# x4to1XTRXv13.net
KiCad netlist of a schematic drawn in Altium Designer
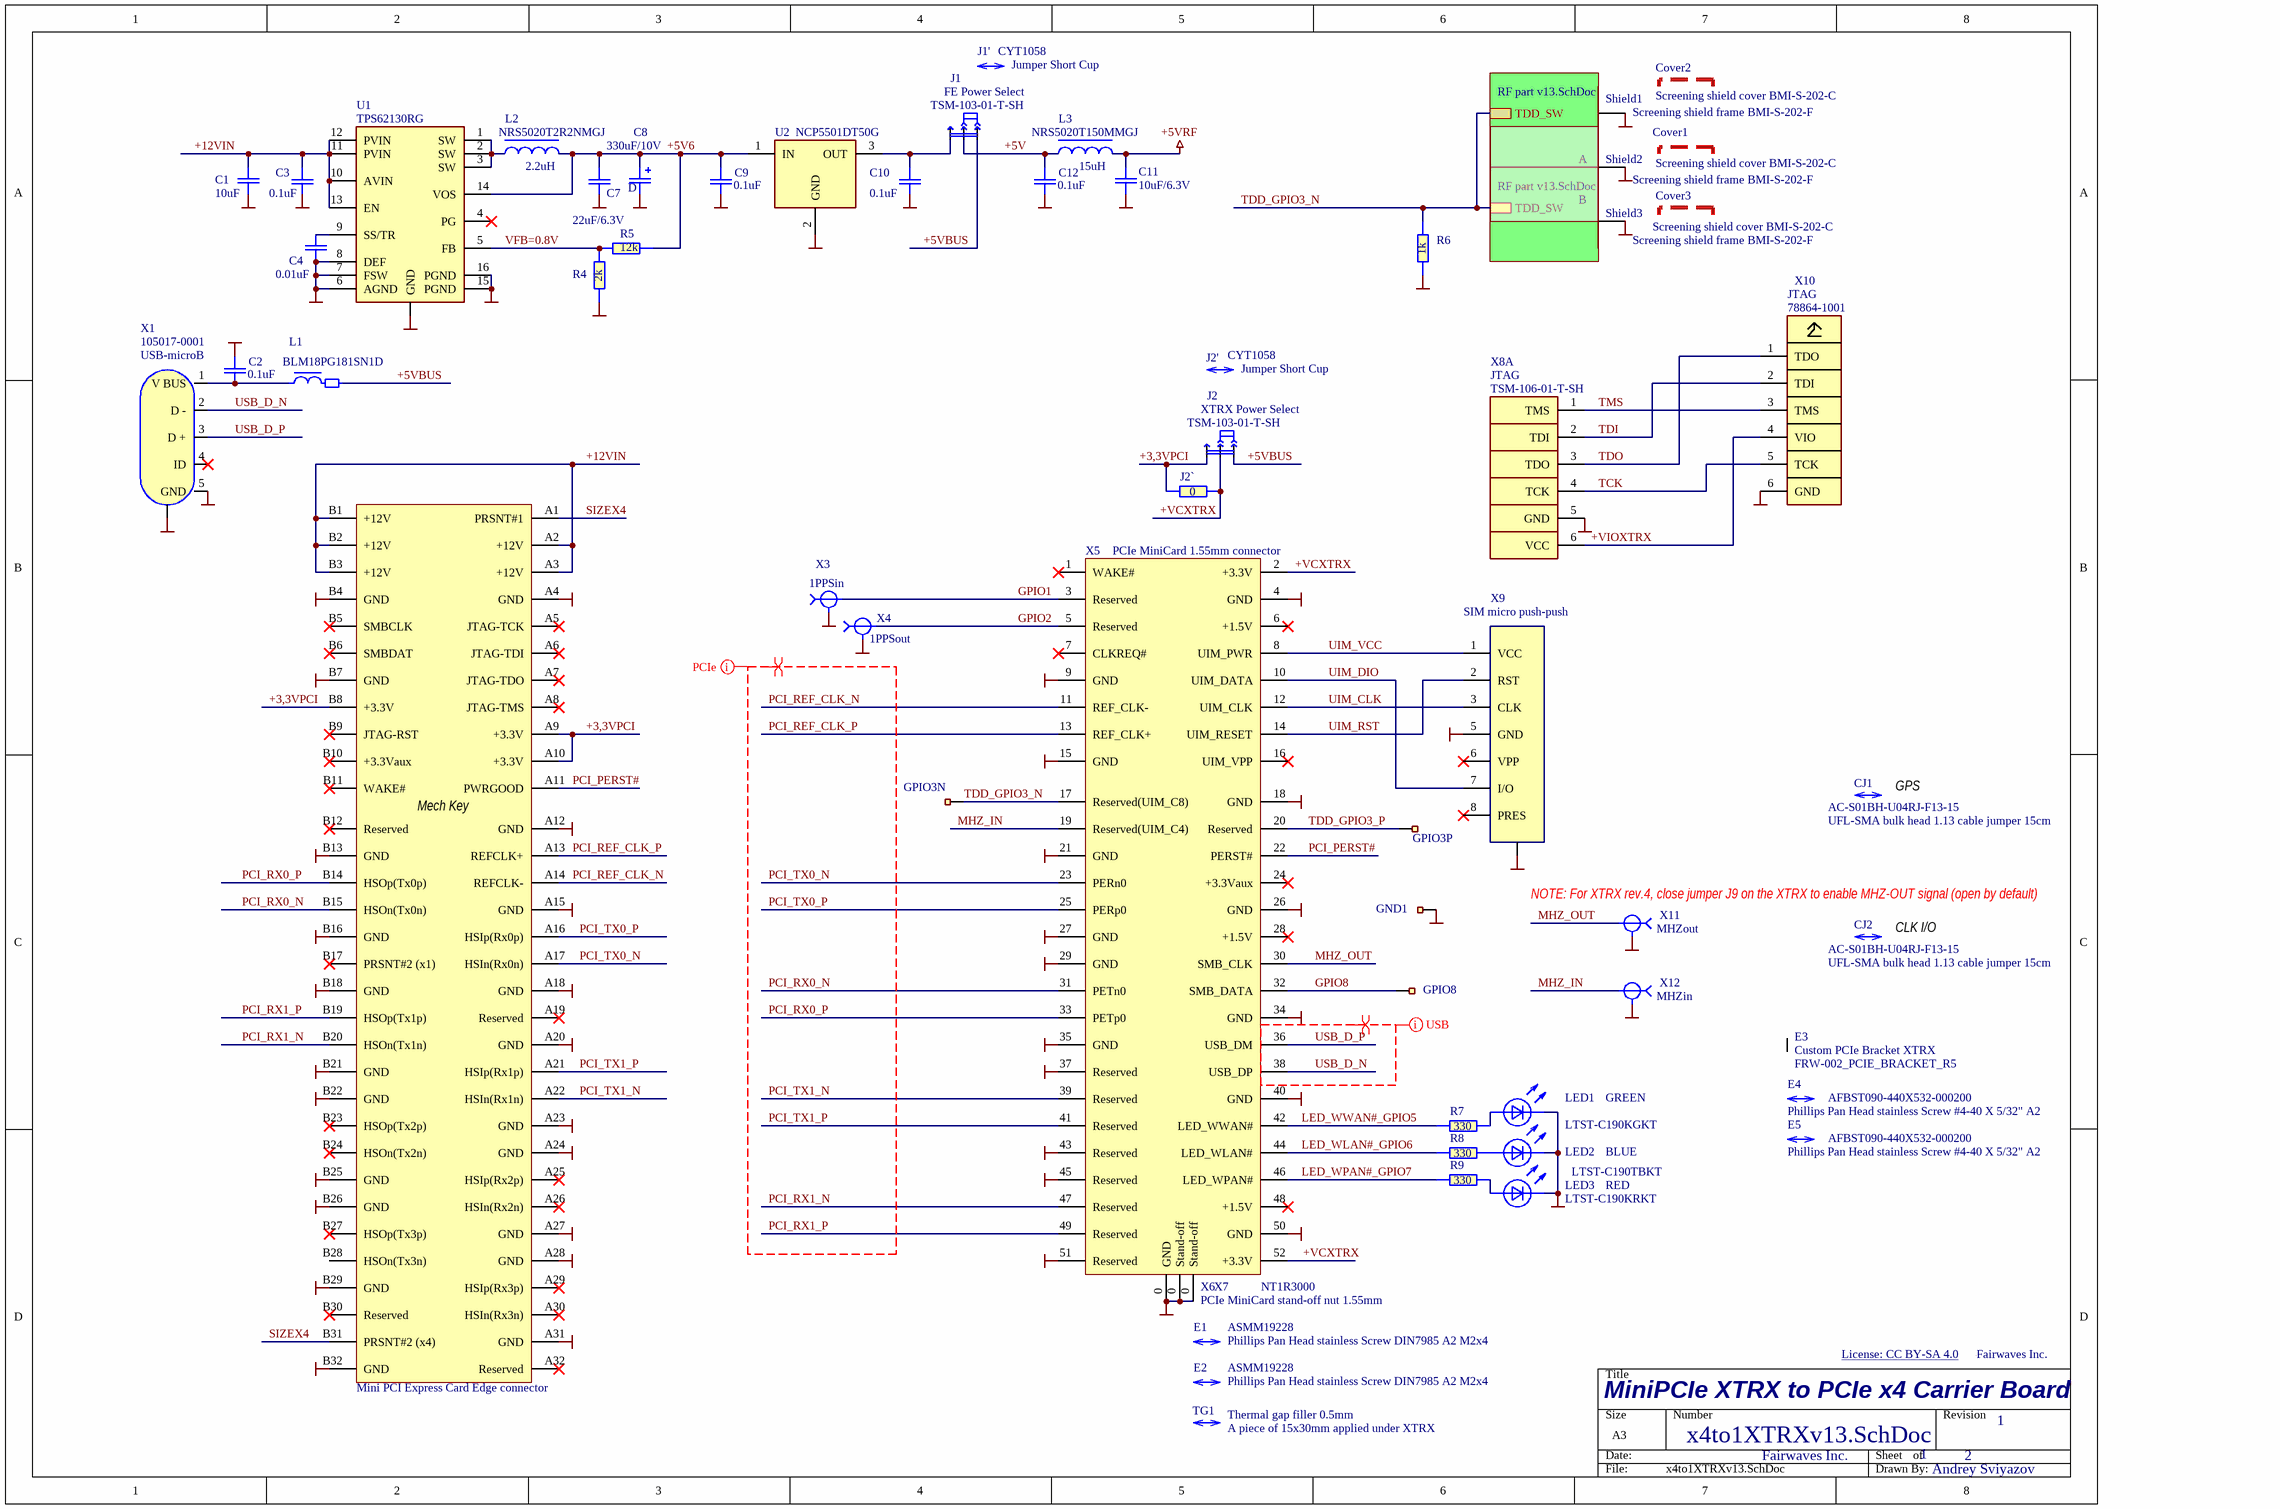
[diagram p0: x4to1XTRXv13.SchDoc]

(export (version "E")
  (design (tool "Eeschema 10.0.6"))
  (components
    (comp (ref "C1")
      (value "10uF")
      (footprint "C0805")
      (description "Capacitor")
      (fields (field (name "MANUFACTURER") "MURATA") (field (name "TOLERANCE") "20%"))
      (libsource (lib "Capacitors") (part "C0805"))
    )
    (comp (ref "C2")
      (value "0.1uF")
      (footprint "C0603-PHILLIPS")
      (description "Capacitor")
      (fields (field (name "MANUFACTURER") "MURATA") (field (name "TOLERANCE") "20%"))
      (libsource (lib "altium-import") (part "root_2_C0603_"))
    )
    (comp (ref "C3")
      (value "0.1uF")
      (footprint "C0603-PHILLIPS")
      (description "Capacitor")
      (fields (field (name "MANUFACTURER") "MURATA") (field (name "TOLERANCE") "20%"))
      (libsource (lib "altium-import") (part "root_2_C0603_"))
    )
    (comp (ref "C4")
      (value "0.01uF")
      (footprint "C0603-PHILLIPS")
      (description "Capacitor")
      (fields (field (name "MANUFACTURER") "MURATA") (field (name "TOLERANCE") "20%"))
      (libsource (lib "Capacitors") (part "C0603"))
    )
    (comp (ref "C7")
      (value "22uF/6.3V")
      (footprint "C0603-PHILLIPS")
      (description "Capacitor")
      (fields (field (name "MANUFACTURER") "MURATA") (field (name "TOLERANCE") "20%"))
      (libsource (lib "altium-import") (part "root_2_C0603_"))
    )
    (comp (ref "C8")
      (value "330uF/10V")
      (footprint "cd7343")
      (description "Capacitor")
      (fields (field (name "MANUFACTURER") "Kemet"))
      (libsource (lib "altium-import") (part "root_0_CD7343_"))
    )
    (comp (ref "C9")
      (value "0.1uF")
      (footprint "C0603-PHILLIPS")
      (description "Capacitor")
      (fields (field (name "MANUFACTURER") "MURATA") (field (name "TOLERANCE") "20%"))
      (libsource (lib "altium-import") (part "root_2_C0603_"))
    )
    (comp (ref "C10")
      (value "0.1uF")
      (footprint "C0603-PHILLIPS")
      (description "Capacitor")
      (fields (field (name "MANUFACTURER") "MURATA") (field (name "TOLERANCE") "20%"))
      (libsource (lib "altium-import") (part "root_2_C0603_"))
    )
    (comp (ref "C11")
      (value "10uF/6.3V")
      (footprint "C0603-Phillips")
      (description "Capacitor")
      (fields (field (name "MANUFACTURER") "MURATA") (field (name "TOLERANCE") "20%"))
      (libsource (lib "") (part "C0603_1"))
    )
    (comp (ref "C12")
      (value "0.1uF")
      (footprint "C0603-PHILLIPS")
      (description "Capacitor")
      (fields (field (name "MANUFACTURER") "MURATA") (field (name "TOLERANCE") "20%"))
      (libsource (lib "altium-import") (part "root_2_C0603_"))
    )
    (comp (ref "CJ1")
      (value "AC-S01BH-U04RJ-F13-15")
      (description "Cable jumper")
      (fields
        (field (name "MANUFACTURER") "RFSupplier")
        (field (name "MISC") "UFL-SMA bulk head 1.13 cable jumper 15cm")
      )
      (libsource (lib "Andy") (part "Mating part"))
    )
    (comp (ref "CJ2")
      (value "AC-S01BH-U04RJ-F13-15")
      (description "Cable jumper")
      (fields
        (field (name "MANUFACTURER") "RFSupplier")
        (field (name "MISC") "UFL-SMA bulk head 1.13 cable jumper 15cm")
      )
      (libsource (lib "Andy") (part "Mating part"))
    )
    (comp (ref "Cover1")
      (value "Screening shield cover BMI-S-202-C")
      (description "Screening shield cover")
      (fields (field (name "MANUFACTURER") "Laird Tech"))
      (libsource (lib "Andy") (part "Screen cover BMI-S-202-C"))
    )
    (comp (ref "Cover2")
      (value "Screening shield cover BMI-S-202-C")
      (description "Screening shield cover")
      (fields (field (name "MANUFACTURER") "Laird Tech"))
      (libsource (lib "Andy") (part "Screen cover BMI-S-202-C"))
    )
    (comp (ref "Cover3")
      (value "Screening shield cover BMI-S-202-C")
      (description "Screening shield cover")
      (fields (field (name "MANUFACTURER") "Laird Tech"))
      (libsource (lib "Andy") (part "Screen cover BMI-S-202-C"))
    )
    (comp (ref "E1")
      (value "ASMM19228")
      (description "Screw M2")
      (fields
        (field (name "MANUFACTURER") "Aspen Fasteners")
        (field (name "MISC") "Phillips Pan Head stainless Screw DIN7985 A2 M2x4")
      )
      (libsource (lib "Andy") (part "Mating subpart 1"))
    )
    (comp (ref "E2")
      (value "ASMM19228")
      (description "Screw M2")
      (fields
        (field (name "MANUFACTURER") "Aspen Fasteners")
        (field (name "MISC") "Phillips Pan Head stainless Screw DIN7985 A2 M2x4")
      )
      (libsource (lib "Andy") (part "Mating subpart 1"))
    )
    (comp (ref "E3")
      (value "Custom PCIe Bracket XTRX")
      (footprint "Custom_PCIe_bracket_XTRX1")
      (description "CNC'ed enclosure component")
      (fields (field (name "ALTIUM_VALUE") "FRW-002_PCIE_BRACKET_R5"))
      (libsource (lib "Andy") (part "PCI_Bracket_XTRX1"))
    )
    (comp (ref "E4")
      (value "AFBST090-440X532-000200")
      (description "Screw #4-40")
      (fields
        (field (name "MANUFACTURER") "Aspen Fasteners")
        (field (name "MISC") "Phillips Pan Head stainless Screw #4-40 X 5/32\" A2")
      )
      (libsource (lib "Andy") (part "Mating subpart 1"))
    )
    (comp (ref "E5")
      (value "AFBST090-440X532-000200")
      (description "Screw #4-40")
      (fields
        (field (name "MANUFACTURER") "Aspen Fasteners")
        (field (name "MISC") "Phillips Pan Head stainless Screw #4-40 X 5/32\" A2")
      )
      (libsource (lib "Andy") (part "Mating subpart 1"))
    )
    (comp (ref "GND1")
      (value "~")
      (footprint "KP-C_d1mm")
      (fields (field (name "MANUFACTURER") "PCB"))
      (libsource (lib "Connectors") (part "KP40X40"))
    )
    (comp (ref "GPIO3N")
      (value "~")
      (footprint "KP-C_d1mm")
      (fields (field (name "MANUFACTURER") "PCB"))
      (libsource (lib "Connectors") (part "KP40X40"))
    )
    (comp (ref "GPIO3P")
      (value "~")
      (footprint "KP-C_d1mm")
      (fields (field (name "MANUFACTURER") "PCB"))
      (libsource (lib "") (part "KP40X40_1"))
    )
    (comp (ref "GPIO8")
      (value "~")
      (footprint "KP-C_d1mm")
      (fields (field (name "MANUFACTURER") "PCB"))
      (libsource (lib "") (part "KP40X40_1"))
    )
    (comp (ref "J1")
      (value "TSM-103-01-T-SH")
      (footprint "Head_Male_3P_R/A_SMD")
      (description "Jumper 3 pin")
      (fields (field (name "MANUFACTURER") "Samtec") (field (name "ALTIUM_VALUE") "FE Power Select"))
      (libsource (lib "Andy") (part "JUMPER_3P R/A SMD"))
    )
    (comp (ref "J1'")
      (value "CYT1058")
      (description "Jumper Short Cup")
      (fields (field (name "MISC") "Jumper Short Cup"))
      (libsource (lib "Andy") (part "Mating part"))
    )
    (comp (ref "J2")
      (value "TSM-103-01-T-SH")
      (footprint "Head_Male_3P_R/A_SMD")
      (description "Jumper 3 pin")
      (fields (field (name "MANUFACTURER") "Samtec") (field (name "ALTIUM_VALUE") "XTRX Power Select"))
      (libsource (lib "Andy") (part "JUMPER_3P R/A SMD"))
    )
    (comp (ref "J2'")
      (value "CYT1058")
      (description "Jumper Short Cup")
      (fields (field (name "MISC") "Jumper Short Cup"))
      (libsource (lib "Andy") (part "Mating part"))
    )
    (comp (ref "J2`")
      (value "0")
      (footprint "R0603-PHILLIPS")
      (description "Jumper")
      (fields (field (name "MANUFACTURER") "YAGEO") (field (name "TOLERANCE") "1%"))
      (libsource (lib "altium-import") (part "root_1_R0603_"))
    )
    (comp (ref "L1")
      (value "BLM18PG181SN1D")
      (footprint "TI160808-Phillips")
      (description "Ferrite Bead EMIFIL")
      (fields (field (name "MANUFACTURER") "MURATA"))
      (libsource (lib "Andy") (part "EMI_BLM18"))
    )
    (comp (ref "L2")
      (value "2.2uH")
      (footprint "L-NRS5030")
      (description "Coil")
      (fields
        (field (name "MANUFACTURER") "Taiyo Yuden")
        (field (name "TOLERANCE") "20%")
        (field (name "NAME") "NRS5020T2R2NMGJ")
      )
      (libsource (lib "Andy") (part "L-NRS50x0"))
    )
    (comp (ref "L3")
      (value "15uH")
      (footprint "L-NRS5030")
      (description "Coil")
      (fields
        (field (name "MANUFACTURER") "Taiyo Yuden")
        (field (name "TOLERANCE") "20%")
        (field (name "NAME") "NRS5020T150MMGJ")
      )
      (libsource (lib "Andy") (part "L-NRS50x0"))
    )
    (comp (ref "LED1")
      (value "LTST-C190KGKT")
      (footprint "Andy:LED-0603GR")
      (description "LED GREEN")
      (fields (field (name "MANUFACTURER") "Lite-On Inc") (field (name "ALTIUM_VALUE") "GREEN"))
      (libsource (lib "Andy") (part "LED0603GR_Lite-On"))
    )
    (comp (ref "LED2")
      (value "LTST-C190TBKT")
      (footprint "Andy:LED-0603BL")
      (description "LED BLUE")
      (fields (field (name "MANUFACTURER") "Lite-On Inc") (field (name "ALTIUM_VALUE") "BLUE"))
      (libsource (lib "Andy") (part "LED0603BU_Lite-On"))
    )
    (comp (ref "LED3")
      (value "LTST-C190KRKT")
      (footprint "Andy:LED-0603RD")
      (description "LED RED")
      (fields (field (name "MANUFACTURER") "Lite-On Inc") (field (name "ALTIUM_VALUE") "RED"))
      (libsource (lib "Andy") (part "LED0603RD_Lite-On"))
    )
    (comp (ref "LOGO1")
      (value "Fairwaves Inc.")
      (footprint "Andy:Logo Fairwaves")
      (libsource (lib "Andy") (part "Logo Fairwaves"))
    )
    (comp (ref "R4")
      (value "2k")
      (footprint "R0603-PHILLIPS")
      (description "Resistor")
      (fields (field (name "MANUFACTURER") "YAGEO") (field (name "TOLERANCE") "1%"))
      (libsource (lib "Resistors") (part "R0603"))
    )
    (comp (ref "R5")
      (value "12k")
      (footprint "R0603-PHILLIPS")
      (description "Resistor")
      (fields (field (name "MANUFACTURER") "YAGEO") (field (name "TOLERANCE") "1%"))
      (libsource (lib "") (part "R0603_1"))
    )
    (comp (ref "R6")
      (value "1k")
      (footprint "R0603-PHILLIPS")
      (description "Resistor")
      (fields (field (name "MANUFACTURER") "YAGEO") (field (name "TOLERANCE") "1%"))
      (libsource (lib "altium-import") (part "root_2_R0603_"))
    )
    (comp (ref "R7")
      (value "330")
      (footprint "R0603-PHILLIPS")
      (description "Resistor")
      (fields (field (name "MANUFACTURER") "YAGEO") (field (name "TOLERANCE") "1%"))
      (libsource (lib "altium-import") (part "root_1_R0603_"))
    )
    (comp (ref "R8")
      (value "330")
      (footprint "R0603-PHILLIPS")
      (description "Resistor")
      (fields (field (name "MANUFACTURER") "YAGEO") (field (name "TOLERANCE") "1%"))
      (libsource (lib "altium-import") (part "root_1_R0603_"))
    )
    (comp (ref "R9")
      (value "330")
      (footprint "R0603-PHILLIPS")
      (description "Resistor")
      (fields (field (name "MANUFACTURER") "YAGEO") (field (name "TOLERANCE") "1%"))
      (libsource (lib "altium-import") (part "root_1_R0603_"))
    )
    (comp (ref "Shield1")
      (value "Screening shield frame BMI-S-202-F")
      (footprint "BMI-S-202-F")
      (description "Screening shield frame")
      (fields (field (name "MANUFACTURER") "Laird Tech"))
      (libsource (lib "Andy") (part "Screen frame BMI-S-202-F"))
    )
    (comp (ref "Shield2")
      (value "Screening shield frame BMI-S-202-F")
      (footprint "BMI-S-202-F")
      (description "Screening shield frame")
      (fields (field (name "MANUFACTURER") "Laird Tech"))
      (libsource (lib "Andy") (part "Screen frame BMI-S-202-F"))
    )
    (comp (ref "Shield3")
      (value "Screening shield frame BMI-S-202-F")
      (footprint "BMI-S-202-F")
      (description "Screening shield frame")
      (fields (field (name "MANUFACTURER") "Laird Tech"))
      (libsource (lib "Andy") (part "Screen frame BMI-S-202-F"))
    )
    (comp (ref "TG1")
      (value "A piece of 15x30mm applied under XTRX")
      (description "Thermal gap filler")
      (fields (field (name "MANUFACTURER") "Wakefield") (field (name "MISC") "Thermal gap filler 0.5mm"))
      (libsource (lib "Andy") (part "Mating subpart 1"))
    )
    (comp (ref "U1")
      (value "TPS62130RG")
      (footprint "QFN16(3x3/0/5mm)-Case485AE")
      (description "IC")
      (fields (field (name "MANUFACTURER") "TI"))
      (libsource (lib "Andy") (part "TPS6213x"))
    )
    (comp (ref "U2")
      (value "NCP5501DT50G")
      (footprint "DPAK-3")
      (description "IC LDO fixed Vo")
      (fields (field (name "MANUFACTURER") "ON Semi"))
      (libsource (lib "Andy") (part "NCP5501DTxxG"))
    )
    (comp (ref "X1")
      (value "105017-0001")
      (footprint "Andy:USB-micro-B")
      (description "Connector microUSB-B")
      (fields (field (name "MANUFACTURER") "MOLEX") (field (name "NAME") "USB-microB"))
      (libsource (lib "Andy") (part "USB-microB_105017-1"))
    )
    (comp (ref "X2")
      (value "Mini PCI Express Card Edge connector")
      (footprint "PCIe x4 edge connector")
      (description "PCIe x4 Card edge connector")
      (libsource (lib "Andy") (part "PCIe x4 Card"))
    )
    (comp (ref "X3")
      (value "0734120110")
      (footprint "U_FL")
      (description "Connector (UMCC)")
      (fields (field (name "MANUFACTURER") "Molex") (field (name "MISC") "1PPSin"))
      (libsource (lib "Andy") (part "U_FL"))
    )
    (comp (ref "X4")
      (value "0734120110")
      (footprint "U_FL")
      (description "Connector (UMCC)")
      (fields (field (name "MANUFACTURER") "Molex") (field (name "MISC") "1PPSout"))
      (libsource (lib "Andy") (part "U_FL"))
    )
    (comp (ref "X5")
      (value "PCIe MiniCard 1.55mm connector")
      (footprint "PCIe MiniCard 1.55mm conn")
      (description "Connector PCIe MiniCard")
      (fields (field (name "MANUFACTURER") "JAE Electronics"))
      (libsource (lib "Andy") (part "PCIe MiniCard conn h1.55mm"))
    )
    (comp (ref "X6")
      (value "NT1R3000")
      (footprint "PCIe MiniCard 1.55mm stand off nut")
      (description "Stand-off nut PCIe MiniCard")
      (fields
        (field (name "MANUFACTURER") "JAE Electronics")
        (field (name "MISC") "PCIe MiniCard stand-off nut 1.55mm")
      )
      (libsource (lib "Andy") (part "PCIe MiniCard nut h1.55mm"))
    )
    (comp (ref "X7")
      (value "NT1R3000")
      (footprint "PCIe MiniCard 1.55mm stand off nut")
      (description "Stand-off nut PCIe MiniCard")
      (fields (field (name "MANUFACTURER") "JAE Electronics"))
      (libsource (lib "Andy") (part "PCIe MiniCard nut h1.55mm"))
    )
    (comp (ref "X8")
      (value "TSM-106-01-T-SH")
      (footprint "Head_Male_6P_R/A_SMD")
      (description "Connector header male")
      (fields (field (name "MANUFACTURER") "Samtec") (field (name "ALTIUM_VALUE") "JTAG"))
      (libsource (lib "Andy") (part "Conn TSM-106-01-T-SH (=M20-89605)"))
    )
    (comp (ref "X9")
      (value "SIM micro push-push")
      (footprint "SIM_SF56S006V4BR2000-dig")
      (description "Connector SIM micro card")
      (fields (field (name "MANUFACTURER") "JAE"))
      (libsource (lib "Andy") (part "SIM micro push-push"))
    )
    (comp (ref "X10")
      (value "JTAG")
      (footprint "Molex 78864-1001")
      (description "Connector board to board")
      (fields (field (name "MANUFACTURER") "Molex") (field (name "NAME") "78864-1001"))
      (libsource (lib "Andy") (part "Conn Molex_788641001"))
    )
    (comp (ref "X11")
      (value "0734120110")
      (footprint "U_FL")
      (description "Connector (UMCC)")
      (fields (field (name "MANUFACTURER") "Molex") (field (name "MISC") "MHZout"))
      (libsource (lib "Andy") (part "U_FL"))
    )
    (comp (ref "X12")
      (value "0734120110")
      (footprint "U_FL")
      (description "Connector (UMCC)")
      (fields (field (name "MANUFACTURER") "Molex") (field (name "MISC") "MHZin"))
      (libsource (lib "Andy") (part "U_FL"))
    )
  )
  (nets
    (net (code "1") (name "+5VRF") (class "Default")
      (node (ref "C11") (pin "2") (pinfunction "2_2") (pintype "passive"))
      (node (ref "L3") (pin "2") (pinfunction "2_2") (pintype "passive"))
    )
    (net (code "2") (name "/+3,3VPCI") (class "Default")
      (node (ref "J2") (pin "3") (pinfunction "3_3") (pintype "passive"))
      (node (ref "J2`") (pin "1") (pinfunction "1_1") (pintype "passive"))
      (node (ref "X2") (pin "A10") (pinfunction "+3.3V_A10") (pintype "passive"))
      (node (ref "X2") (pin "A9") (pinfunction "+3.3V_A9") (pintype "passive"))
      (node (ref "X2") (pin "B8") (pinfunction "+3.3V_B8") (pintype "passive"))
    )
    (net (code "3") (name "/+5V") (class "Default")
      (node (ref "C12") (pin "2") (pinfunction "2_2") (pintype "passive"))
      (node (ref "J1") (pin "2") (pinfunction "2_2") (pintype "passive"))
      (node (ref "L3") (pin "1") (pinfunction "1_1") (pintype "passive"))
    )
    (net (code "4") (name "/+5V6") (class "Default")
      (node (ref "C7") (pin "2") (pinfunction "2_2") (pintype "passive"))
      (node (ref "C8") (pin "1") (pinfunction "+_1") (pintype "passive"))
      (node (ref "C9") (pin "2") (pinfunction "2_2") (pintype "passive"))
      (node (ref "L2") (pin "2") (pinfunction "2_2") (pintype "passive"))
      (node (ref "R5") (pin "2") (pinfunction "2_2") (pintype "passive"))
      (node (ref "U1") (pin "14") (pinfunction "VOS_14") (pintype "passive"))
      (node (ref "U2") (pin "1") (pinfunction "IN_1") (pintype "passive"))
    )
    (net (code "5") (name "/+5VBUS") (class "Default")
      (node (ref "J1") (pin "1") (pinfunction "1_1") (pintype "passive"))
      (node (ref "J2") (pin "1") (pinfunction "1_1") (pintype "passive"))
      (node (ref "L1") (pin "2") (pinfunction "2_2") (pintype "passive"))
    )
    (net (code "6") (name "/+12VIN") (class "Default")
      (node (ref "C1") (pin "1") (pinfunction "1_1") (pintype "passive"))
      (node (ref "C3") (pin "2") (pinfunction "2_2") (pintype "passive"))
      (node (ref "U1") (pin "10") (pinfunction "AVIN_10") (pintype "passive"))
      (node (ref "U1") (pin "11") (pinfunction "PVIN_11") (pintype "passive"))
      (node (ref "U1") (pin "12") (pinfunction "PVIN_12") (pintype "passive"))
      (node (ref "U1") (pin "13") (pinfunction "EN_13") (pintype "passive"))
      (node (ref "X2") (pin "A2") (pinfunction "+12V_A2") (pintype "passive"))
      (node (ref "X2") (pin "A3") (pinfunction "+12V_A3") (pintype "passive"))
      (node (ref "X2") (pin "B1") (pinfunction "+12V_B1") (pintype "passive"))
      (node (ref "X2") (pin "B2") (pinfunction "+12V_B2") (pintype "passive"))
      (node (ref "X2") (pin "B3") (pinfunction "+12V_B3") (pintype "passive"))
    )
    (net (code "7") (name "/+VCXTRX") (class "Default")
      (node (ref "J2") (pin "2") (pinfunction "2_2") (pintype "passive"))
      (node (ref "J2`") (pin "2") (pinfunction "2_2") (pintype "passive"))
      (node (ref "X5") (pin "2") (pinfunction "+3.3V_2") (pintype "passive"))
      (node (ref "X5") (pin "52") (pinfunction "+3.3V_52") (pintype "passive"))
    )
    (net (code "8") (name "/+VIOXTRX") (class "Default")
      (node (ref "X10") (pin "4") (pinfunction "VIO_4") (pintype "passive"))
      (node (ref "X8") (pin "6") (pinfunction "TMS_6") (pintype "passive"))
    )
    (net (code "9") (name "/GPIO1") (class "Default")
      (node (ref "X3") (pin "1") (pinfunction "1_1") (pintype "passive"))
      (node (ref "X5") (pin "3") (pinfunction "Reserved_3") (pintype "passive"))
    )
    (net (code "10") (name "/GPIO2") (class "Default")
      (node (ref "X4") (pin "1") (pinfunction "1_1") (pintype "passive"))
      (node (ref "X5") (pin "5") (pinfunction "Reserved_5") (pintype "passive"))
    )
    (net (code "11") (name "/GPIO8") (class "Default")
      (node (ref "GPIO8") (pin "1") (pinfunction "1_1") (pintype "passive"))
      (node (ref "X5") (pin "32") (pinfunction "SMB_DATA_32") (pintype "passive"))
    )
    (net (code "12") (name "/LED_WLAN#_GPIO6") (class "Default")
      (node (ref "R8") (pin "1") (pinfunction "1_1") (pintype "passive"))
      (node (ref "X5") (pin "44") (pinfunction "LED_WLAN#_44") (pintype "passive"))
    )
    (net (code "13") (name "/LED_WPAN#_GPIO7") (class "Default")
      (node (ref "R9") (pin "1") (pinfunction "1_1") (pintype "passive"))
      (node (ref "X5") (pin "46") (pinfunction "LED_WPAN#_46") (pintype "passive"))
    )
    (net (code "14") (name "/LED_WWAN#_GPIO5") (class "Default")
      (node (ref "R7") (pin "1") (pinfunction "1_1") (pintype "passive"))
      (node (ref "X5") (pin "42") (pinfunction "LED_WWAN#_42") (pintype "passive"))
    )
    (net (code "15") (name "/MHZ_IN") (class "Default")
      (node (ref "X12") (pin "1") (pinfunction "1_1") (pintype "passive"))
      (node (ref "X5") (pin "19") (pinfunction "Reserved(UIM_C4)_19") (pintype "passive"))
    )
    (net (code "16") (name "/MHZ_OUT") (class "Default")
      (node (ref "X11") (pin "1") (pinfunction "1_1") (pintype "passive"))
      (node (ref "X5") (pin "30") (pinfunction "SMB_CLK_30") (pintype "passive"))
    )
    (net (code "17") (name "/PCI_PERST#") (class "Default")
      (node (ref "X2") (pin "A11") (pinfunction "PWRGOOD_A11") (pintype "passive"))
      (node (ref "X5") (pin "22") (pinfunction "PERST#_22") (pintype "passive"))
    )
    (net (code "18") (name "/PCI_REF_CLK_N") (class "Default")
      (node (ref "X2") (pin "A14") (pinfunction "REFCLK-_A14") (pintype "passive"))
      (node (ref "X5") (pin "11") (pinfunction "REF_CLK-_11") (pintype "passive"))
    )
    (net (code "19") (name "/PCI_REF_CLK_P") (class "Default")
      (node (ref "X2") (pin "A13") (pinfunction "REFCLK+_A13") (pintype "passive"))
      (node (ref "X5") (pin "13") (pinfunction "REF_CLK+_13") (pintype "passive"))
    )
    (net (code "20") (name "/PCI_RX0_N") (class "Default")
      (node (ref "X2") (pin "B15") (pinfunction "HSOn(Tx0n)_B15") (pintype "passive"))
      (node (ref "X5") (pin "31") (pinfunction "PETn0_31") (pintype "passive"))
    )
    (net (code "21") (name "/PCI_RX0_P") (class "Default")
      (node (ref "X2") (pin "B14") (pinfunction "HSOp(Tx0p)_B14") (pintype "passive"))
      (node (ref "X5") (pin "33") (pinfunction "PETp0_33") (pintype "passive"))
    )
    (net (code "22") (name "/PCI_RX1_N") (class "Default")
      (node (ref "X2") (pin "B20") (pinfunction "HSOn(Tx1n)_B20") (pintype "passive"))
      (node (ref "X5") (pin "47") (pinfunction "Reserved_47") (pintype "passive"))
    )
    (net (code "23") (name "/PCI_RX1_P") (class "Default")
      (node (ref "X2") (pin "B19") (pinfunction "HSOp(Tx1p)_B19") (pintype "passive"))
      (node (ref "X5") (pin "49") (pinfunction "Reserved_49") (pintype "passive"))
    )
    (net (code "24") (name "/PCI_TX0_N") (class "Default")
      (node (ref "X2") (pin "A17") (pinfunction "HSIn(Rx0n)_A17") (pintype "passive"))
      (node (ref "X5") (pin "23") (pinfunction "PERn0_23") (pintype "passive"))
    )
    (net (code "25") (name "/PCI_TX0_P") (class "Default")
      (node (ref "X2") (pin "A16") (pinfunction "HSIp(Rx0p)_A16") (pintype "passive"))
      (node (ref "X5") (pin "25") (pinfunction "PERp0_25") (pintype "passive"))
    )
    (net (code "26") (name "/PCI_TX1_N") (class "Default")
      (node (ref "X2") (pin "A22") (pinfunction "HSIn(Rx1n)_A22") (pintype "passive"))
      (node (ref "X5") (pin "39") (pinfunction "Reserved_39") (pintype "passive"))
    )
    (net (code "27") (name "/PCI_TX1_P") (class "Default")
      (node (ref "X2") (pin "A21") (pinfunction "HSIp(Rx1p)_A21") (pintype "passive"))
      (node (ref "X5") (pin "41") (pinfunction "Reserved_41") (pintype "passive"))
    )
    (net (code "28") (name "/SIZEX4") (class "Default")
      (node (ref "X2") (pin "A1") (pinfunction "PRSNT#1_A1") (pintype "passive"))
      (node (ref "X2") (pin "B31") (pinfunction "PRSNT#2_(x4)_B31") (pintype "passive"))
    )
    (net (code "29") (name "/TCK") (class "Default")
      (node (ref "X10") (pin "5") (pinfunction "TCK_5") (pintype "passive"))
      (node (ref "X8") (pin "4") (pinfunction "TDO_4") (pintype "passive"))
    )
    (net (code "30") (name "/TDD_GPIO3_N") (class "Default")
      (node (ref "GPIO3N") (pin "1") (pinfunction "1_1") (pintype "passive"))
      (node (ref "R6") (pin "2") (pinfunction "2_2") (pintype "passive"))
      (node (ref "X5") (pin "17") (pinfunction "Reserved(UIM_C8)_17") (pintype "passive"))
    )
    (net (code "31") (name "/TDD_GPIO3_P") (class "Default")
      (node (ref "GPIO3P") (pin "1") (pinfunction "1_1") (pintype "passive"))
      (node (ref "X5") (pin "20") (pinfunction "Reserved_20") (pintype "passive"))
    )
    (net (code "32") (name "/TDI") (class "Default")
      (node (ref "X10") (pin "2") (pinfunction "TDI_2") (pintype "passive"))
      (node (ref "X8") (pin "2") (pinfunction "GND_2") (pintype "passive"))
    )
    (net (code "33") (name "/TDO") (class "Default")
      (node (ref "X10") (pin "1") (pinfunction "TDO_1") (pintype "passive"))
      (node (ref "X8") (pin "3") (pinfunction "TDO_3") (pintype "passive"))
    )
    (net (code "34") (name "/TMS") (class "Default")
      (node (ref "X10") (pin "3") (pinfunction "TMS_3") (pintype "passive"))
      (node (ref "X8") (pin "1") (pinfunction "VCC_1") (pintype "passive"))
    )
    (net (code "35") (name "/UIM_CLK") (class "Default")
      (node (ref "X5") (pin "12") (pinfunction "UIM_CLK_12") (pintype "passive"))
      (node (ref "X9") (pin "3") (pinfunction "CLK_3") (pintype "passive"))
    )
    (net (code "36") (name "/UIM_DIO") (class "Default")
      (node (ref "X5") (pin "10") (pinfunction "UIM_DATA_10") (pintype "passive"))
      (node (ref "X9") (pin "7") (pinfunction "I/O_7") (pintype "passive"))
    )
    (net (code "37") (name "/UIM_RST") (class "Default")
      (node (ref "X5") (pin "14") (pinfunction "UIM_RESET_14") (pintype "passive"))
      (node (ref "X9") (pin "2") (pinfunction "RST_2") (pintype "passive"))
    )
    (net (code "38") (name "/UIM_VCC") (class "Default")
      (node (ref "X5") (pin "8") (pinfunction "UIM_PWR_8") (pintype "passive"))
      (node (ref "X9") (pin "1") (pinfunction "VCC_1") (pintype "passive"))
    )
    (net (code "39") (name "/USB_D_N") (class "Default")
      (node (ref "X1") (pin "2") (pinfunction "D_-_2") (pintype "passive"))
      (node (ref "X5") (pin "38") (pinfunction "USB_DP_38") (pintype "passive"))
    )
    (net (code "40") (name "/USB_D_P") (class "Default")
      (node (ref "X1") (pin "3") (pinfunction "D_+_3") (pintype "passive"))
      (node (ref "X5") (pin "36") (pinfunction "USB_DM_36") (pintype "passive"))
    )
    (net (code "41") (name "GND") (class "Default")
      (node (ref "C1") (pin "2") (pinfunction "2_2") (pintype "passive"))
      (node (ref "C10") (pin "1") (pinfunction "1_1") (pintype "passive"))
      (node (ref "C11") (pin "1") (pinfunction "1_1") (pintype "passive"))
      (node (ref "C12") (pin "1") (pinfunction "1_1") (pintype "passive"))
      (node (ref "C2") (pin "2") (pinfunction "2_2") (pintype "passive"))
      (node (ref "C3") (pin "1") (pinfunction "1_1") (pintype "passive"))
      (node (ref "C4") (pin "2") (pinfunction "2_2") (pintype "passive"))
      (node (ref "C7") (pin "1") (pinfunction "1_1") (pintype "passive"))
      (node (ref "C8") (pin "2") (pinfunction "-_2") (pintype "passive"))
      (node (ref "C9") (pin "1") (pinfunction "1_1") (pintype "passive"))
      (node (ref "GND1") (pin "1") (pinfunction "1_1") (pintype "passive"))
      (node (ref "LED1") (pin "1") (pinfunction "K_1") (pintype "passive"))
      (node (ref "LED2") (pin "1") (pinfunction "K_1") (pintype "passive"))
      (node (ref "LED3") (pin "1") (pinfunction "K_1") (pintype "passive"))
      (node (ref "R4") (pin "2") (pinfunction "2_2") (pintype "passive"))
      (node (ref "R6") (pin "1") (pinfunction "1_1") (pintype "passive"))
      (node (ref "Shield1") (pin "0") (pinfunction "GND_0") (pintype "passive"))
      (node (ref "Shield2") (pin "0") (pinfunction "GND_0") (pintype "passive"))
      (node (ref "Shield3") (pin "0") (pinfunction "GND_0") (pintype "passive"))
      (node (ref "U1") (pin "0") (pinfunction "GND_0") (pintype "passive"))
      (node (ref "U1") (pin "15") (pinfunction "PGND_15") (pintype "passive"))
      (node (ref "U1") (pin "16") (pinfunction "PGND_16") (pintype "passive"))
      (node (ref "U1") (pin "6") (pinfunction "AGND_6") (pintype "passive"))
      (node (ref "U1") (pin "7") (pinfunction "FSW_7") (pintype "passive"))
      (node (ref "U1") (pin "8") (pinfunction "DEF_8") (pintype "passive"))
      (node (ref "U2") (pin "2") (pinfunction "GND_2") (pintype "passive"))
      (node (ref "X1") (pin "0") (pinfunction "GND_0") (pintype "passive"))
      (node (ref "X1") (pin "5") (pinfunction "GND_5") (pintype "passive"))
      (node (ref "X10") (pin "6") (pinfunction "GND_6") (pintype "passive"))
      (node (ref "X11") (pin "2") (pinfunction "GND_2") (pintype "passive"))
      (node (ref "X12") (pin "2") (pinfunction "GND_2") (pintype "passive"))
      (node (ref "X2") (pin "A12") (pinfunction "GND_A12") (pintype "passive"))
      (node (ref "X2") (pin "A15") (pinfunction "GND_A15") (pintype "passive"))
      (node (ref "X2") (pin "A18") (pinfunction "GND_A18") (pintype "passive"))
      (node (ref "X2") (pin "A20") (pinfunction "GND_A20") (pintype "passive"))
      (node (ref "X2") (pin "A23") (pinfunction "GND_A23") (pintype "passive"))
      (node (ref "X2") (pin "A24") (pinfunction "GND_A24") (pintype "passive"))
      (node (ref "X2") (pin "A27") (pinfunction "GND_A27") (pintype "passive"))
      (node (ref "X2") (pin "A28") (pinfunction "GND_A28") (pintype "passive"))
      (node (ref "X2") (pin "A31") (pinfunction "GND_A31") (pintype "passive"))
      (node (ref "X2") (pin "A4") (pinfunction "GND_A4") (pintype "passive"))
      (node (ref "X2") (pin "B13") (pinfunction "GND_B13") (pintype "passive"))
      (node (ref "X2") (pin "B16") (pinfunction "GND_B16") (pintype "passive"))
      (node (ref "X2") (pin "B18") (pinfunction "GND_B18") (pintype "passive"))
      (node (ref "X2") (pin "B21") (pinfunction "GND_B21") (pintype "passive"))
      (node (ref "X2") (pin "B22") (pinfunction "GND_B22") (pintype "passive"))
      (node (ref "X2") (pin "B25") (pinfunction "GND_B25") (pintype "passive"))
      (node (ref "X2") (pin "B26") (pinfunction "GND_B26") (pintype "passive"))
      (node (ref "X2") (pin "B29") (pinfunction "GND_B29") (pintype "passive"))
      (node (ref "X2") (pin "B32") (pinfunction "GND_B32") (pintype "passive"))
      (node (ref "X2") (pin "B4") (pinfunction "GND_B4") (pintype "passive"))
      (node (ref "X2") (pin "B7") (pinfunction "GND_B7") (pintype "passive"))
      (node (ref "X3") (pin "2") (pinfunction "GND_2") (pintype "passive"))
      (node (ref "X4") (pin "2") (pinfunction "GND_2") (pintype "passive"))
      (node (ref "X5") (pin "0") (pinfunction "GND_0") (pintype "passive"))
      (node (ref "X5") (pin "15") (pinfunction "GND_15") (pintype "passive"))
      (node (ref "X5") (pin "18") (pinfunction "GND_18") (pintype "passive"))
      (node (ref "X5") (pin "21") (pinfunction "GND_21") (pintype "passive"))
      (node (ref "X5") (pin "26") (pinfunction "GND_26") (pintype "passive"))
      (node (ref "X5") (pin "27") (pinfunction "GND_27") (pintype "passive"))
      (node (ref "X5") (pin "29") (pinfunction "GND_29") (pintype "passive"))
      (node (ref "X5") (pin "34") (pinfunction "GND_34") (pintype "passive"))
      (node (ref "X5") (pin "35") (pinfunction "GND_35") (pintype "passive"))
      (node (ref "X5") (pin "37") (pinfunction "Reserved_37") (pintype "passive"))
      (node (ref "X5") (pin "4") (pinfunction "GND_4") (pintype "passive"))
      (node (ref "X5") (pin "40") (pinfunction "GND_40") (pintype "passive"))
      (node (ref "X5") (pin "43") (pinfunction "Reserved_43") (pintype "passive"))
      (node (ref "X5") (pin "45") (pinfunction "Reserved_45") (pintype "passive"))
      (node (ref "X5") (pin "50") (pinfunction "GND_50") (pintype "passive"))
      (node (ref "X5") (pin "51") (pinfunction "Reserved_51") (pintype "passive"))
      (node (ref "X5") (pin "9") (pinfunction "GND_9") (pintype "passive"))
      (node (ref "X6") (pin "0") (pinfunction "Stand-off_0") (pintype "passive"))
      (node (ref "X7") (pin "0") (pinfunction "Stand-off_0") (pintype "passive"))
      (node (ref "X8") (pin "5") (pinfunction "TDI_5") (pintype "passive"))
      (node (ref "X9") (pin "0") (pinfunction "GND_0") (pintype "passive"))
      (node (ref "X9") (pin "5") (pinfunction "GND_5") (pintype "passive"))
    )
    (net (code "42") (name "Net-(L2-Pad1)") (class "Default")
      (node (ref "L2") (pin "1") (pinfunction "1_1") (pintype "passive"))
      (node (ref "U1") (pin "1") (pinfunction "SW_1") (pintype "passive"))
      (node (ref "U1") (pin "2") (pinfunction "SW_2") (pintype "passive"))
      (node (ref "U1") (pin "3") (pinfunction "SW_3") (pintype "passive"))
    )
    (net (code "43") (name "Net-(LED1-A)") (class "Default")
      (node (ref "LED1") (pin "2") (pinfunction "A_2") (pintype "passive"))
      (node (ref "R7") (pin "2") (pinfunction "2_2") (pintype "passive"))
    )
    (net (code "44") (name "Net-(LED2-A)") (class "Default")
      (node (ref "LED2") (pin "2") (pinfunction "A_2") (pintype "passive"))
      (node (ref "R8") (pin "2") (pinfunction "2_2") (pintype "passive"))
    )
    (net (code "45") (name "Net-(LED3-A)") (class "Default")
      (node (ref "LED3") (pin "2") (pinfunction "A_2") (pintype "passive"))
      (node (ref "R9") (pin "2") (pinfunction "2_2") (pintype "passive"))
    )
    (net (code "46") (name "Net-(U1-FB)") (class "Default")
      (node (ref "R4") (pin "1") (pinfunction "1_1") (pintype "passive"))
      (node (ref "R5") (pin "1") (pinfunction "1_1") (pintype "passive"))
      (node (ref "U1") (pin "5") (pinfunction "FB_5") (pintype "passive"))
    )
    (net (code "47") (name "Net-(U1-SS{slash}TR)") (class "Default")
      (node (ref "C4") (pin "1") (pinfunction "1_1") (pintype "passive"))
      (node (ref "U1") (pin "9") (pinfunction "SS/TR_9") (pintype "passive"))
    )
    (net (code "48") (name "Net-(U2-OUT)") (class "Default")
      (node (ref "C10") (pin "2") (pinfunction "2_2") (pintype "passive"))
      (node (ref "J1") (pin "3") (pinfunction "3_3") (pintype "passive"))
      (node (ref "U2") (pin "3") (pinfunction "OUT_3") (pintype "passive"))
    )
    (net (code "49") (name "Net-(X1-V_BUS)") (class "Default")
      (node (ref "C2") (pin "1") (pinfunction "1_1") (pintype "passive"))
      (node (ref "L1") (pin "1") (pinfunction "1_1") (pintype "passive"))
      (node (ref "X1") (pin "1") (pinfunction "V_BUS_1") (pintype "power_in"))
    )
    (net (code "50") (name "unconnected-(CJ1-Pad)") (class "Default")
      (node (ref "CJ1") (pin "") (pintype "passive"))
    )
    (net (code "51") (name "unconnected-(CJ2-Pad)") (class "Default")
      (node (ref "CJ2") (pin "") (pintype "passive"))
    )
    (net (code "52") (name "unconnected-(E1-Pad)") (class "Default")
      (node (ref "E1") (pin "") (pintype "passive"))
    )
    (net (code "53") (name "unconnected-(E2-Pad)") (class "Default")
      (node (ref "E2") (pin "") (pintype "passive"))
    )
    (net (code "54") (name "unconnected-(E3-Pad0)") (class "Default")
      (node (ref "E3") (pin "0") (pinfunction "0_0") (pintype "passive"))
    )
    (net (code "55") (name "unconnected-(E4-Pad)") (class "Default")
      (node (ref "E4") (pin "") (pintype "passive"))
    )
    (net (code "56") (name "unconnected-(E5-Pad)") (class "Default")
      (node (ref "E5") (pin "") (pintype "passive"))
    )
    (net (code "57") (name "unconnected-(J1'-Pad)") (class "Default")
      (node (ref "J1'") (pin "") (pintype "passive"))
    )
    (net (code "58") (name "unconnected-(J2'-Pad)") (class "Default")
      (node (ref "J2'") (pin "") (pintype "passive"))
    )
    (net (code "59") (name "unconnected-(LOGO1-Pad1)") (class "Default")
      (node (ref "LOGO1") (pin "1") (pinfunction "1_1") (pintype "passive"))
    )
    (net (code "60") (name "unconnected-(TG1-Pad)") (class "Default")
      (node (ref "TG1") (pin "") (pintype "passive"))
    )
    (net (code "61") (name "unconnected-(U1-PG-Pad4)") (class "Default")
      (node (ref "U1") (pin "4") (pinfunction "PG_4") (pintype "passive+no_connect"))
    )
    (net (code "62") (name "unconnected-(X1-ID-Pad4)") (class "Default")
      (node (ref "X1") (pin "4") (pinfunction "ID_4") (pintype "passive+no_connect"))
    )
    (net (code "63") (name "unconnected-(X2-+3.3Vaux-PadB10)") (class "Default")
      (node (ref "X2") (pin "B10") (pinfunction "+3.3Vaux_B10") (pintype "passive+no_connect"))
    )
    (net (code "64") (name "unconnected-(X2-HSIn(Rx2n)-PadA26)") (class "Default")
      (node (ref "X2") (pin "A26") (pinfunction "HSIn(Rx2n)_A26") (pintype "passive+no_connect"))
    )
    (net (code "65") (name "unconnected-(X2-HSIn(Rx3n)-PadA30)") (class "Default")
      (node (ref "X2") (pin "A30") (pinfunction "HSIn(Rx3n)_A30") (pintype "passive+no_connect"))
    )
    (net (code "66") (name "unconnected-(X2-HSIp(Rx2p)-PadA25)") (class "Default")
      (node (ref "X2") (pin "A25") (pinfunction "HSIp(Rx2p)_A25") (pintype "passive+no_connect"))
    )
    (net (code "67") (name "unconnected-(X2-HSIp(Rx3p)-PadA29)") (class "Default")
      (node (ref "X2") (pin "A29") (pinfunction "HSIp(Rx3p)_A29") (pintype "passive+no_connect"))
    )
    (net (code "68") (name "unconnected-(X2-HSOn(Tx2n)-PadB24)") (class "Default")
      (node (ref "X2") (pin "B24") (pinfunction "HSOn(Tx2n)_B24") (pintype "passive+no_connect"))
    )
    (net (code "69") (name "unconnected-(X2-HSOn(Tx3n)-PadB28)") (class "Default")
      (node (ref "X2") (pin "B28") (pinfunction "HSOn(Tx3n)_B28") (pintype "passive"))
    )
    (net (code "70") (name "unconnected-(X2-HSOp(Tx2p)-PadB23)") (class "Default")
      (node (ref "X2") (pin "B23") (pinfunction "HSOp(Tx2p)_B23") (pintype "passive+no_connect"))
    )
    (net (code "71") (name "unconnected-(X2-HSOp(Tx3p)-PadB27)") (class "Default")
      (node (ref "X2") (pin "B27") (pinfunction "HSOp(Tx3p)_B27") (pintype "passive+no_connect"))
    )
    (net (code "72") (name "unconnected-(X2-JTAG-RST-PadB9)") (class "Default")
      (node (ref "X2") (pin "B9") (pinfunction "JTAG-RST_B9") (pintype "passive+no_connect"))
    )
    (net (code "73") (name "unconnected-(X2-JTAG-TCK-PadA5)") (class "Default")
      (node (ref "X2") (pin "A5") (pinfunction "JTAG-TCK_A5") (pintype "passive+no_connect"))
    )
    (net (code "74") (name "unconnected-(X2-JTAG-TDI-PadA6)") (class "Default")
      (node (ref "X2") (pin "A6") (pinfunction "JTAG-TDI_A6") (pintype "passive+no_connect"))
    )
    (net (code "75") (name "unconnected-(X2-JTAG-TDO-PadA7)") (class "Default")
      (node (ref "X2") (pin "A7") (pinfunction "JTAG-TDO_A7") (pintype "passive+no_connect"))
    )
    (net (code "76") (name "unconnected-(X2-JTAG-TMS-PadA8)") (class "Default")
      (node (ref "X2") (pin "A8") (pinfunction "JTAG-TMS_A8") (pintype "passive+no_connect"))
    )
    (net (code "77") (name "unconnected-(X2-PRSNT#2_(x1)-PadB17)") (class "Default")
      (node (ref "X2") (pin "B17") (pinfunction "PRSNT#2_(x1)_B17") (pintype "passive+no_connect"))
    )
    (net (code "78") (name "unconnected-(X2-Reserved-PadA19)") (class "Default")
      (node (ref "X2") (pin "A19") (pinfunction "Reserved_A19") (pintype "passive+no_connect"))
    )
    (net (code "79") (name "unconnected-(X2-Reserved-PadA32)") (class "Default")
      (node (ref "X2") (pin "A32") (pinfunction "Reserved_A32") (pintype "passive+no_connect"))
    )
    (net (code "80") (name "unconnected-(X2-Reserved-PadB12)") (class "Default")
      (node (ref "X2") (pin "B12") (pinfunction "Reserved_B12") (pintype "passive+no_connect"))
    )
    (net (code "81") (name "unconnected-(X2-Reserved-PadB30)") (class "Default")
      (node (ref "X2") (pin "B30") (pinfunction "Reserved_B30") (pintype "passive+no_connect"))
    )
    (net (code "82") (name "unconnected-(X2-SMBCLK-PadB5)") (class "Default")
      (node (ref "X2") (pin "B5") (pinfunction "SMBCLK_B5") (pintype "passive+no_connect"))
    )
    (net (code "83") (name "unconnected-(X2-SMBDAT-PadB6)") (class "Default")
      (node (ref "X2") (pin "B6") (pinfunction "SMBDAT_B6") (pintype "passive+no_connect"))
    )
    (net (code "84") (name "unconnected-(X2-WAKE#-PadB11)") (class "Default")
      (node (ref "X2") (pin "B11") (pinfunction "WAKE#_B11") (pintype "passive+no_connect"))
    )
    (net (code "85") (name "unconnected-(X5-+1.5V-Pad6)") (class "Default")
      (node (ref "X5") (pin "6") (pinfunction "+1.5V_6") (pintype "passive+no_connect"))
    )
    (net (code "86") (name "unconnected-(X5-+1.5V-Pad28)") (class "Default")
      (node (ref "X5") (pin "28") (pinfunction "+1.5V_28") (pintype "passive+no_connect"))
    )
    (net (code "87") (name "unconnected-(X5-+1.5V-Pad48)") (class "Default")
      (node (ref "X5") (pin "48") (pinfunction "+1.5V_48") (pintype "passive+no_connect"))
    )
    (net (code "88") (name "unconnected-(X5-+3.3Vaux-Pad24)") (class "Default")
      (node (ref "X5") (pin "24") (pinfunction "+3.3Vaux_24") (pintype "passive+no_connect"))
    )
    (net (code "89") (name "unconnected-(X5-CLKREQ#-Pad7)") (class "Default")
      (node (ref "X5") (pin "7") (pinfunction "CLKREQ#_7") (pintype "passive+no_connect"))
    )
    (net (code "90") (name "unconnected-(X5-UIM_VPP-Pad16)") (class "Default")
      (node (ref "X5") (pin "16") (pinfunction "UIM_VPP_16") (pintype "passive+no_connect"))
    )
    (net (code "91") (name "unconnected-(X5-WAKE#-Pad1)") (class "Default")
      (node (ref "X5") (pin "1") (pinfunction "WAKE#_1") (pintype "passive+no_connect"))
    )
    (net (code "92") (name "unconnected-(X9-PRES-Pad8)") (class "Default")
      (node (ref "X9") (pin "8") (pinfunction "PRES_8") (pintype "passive+no_connect"))
    )
    (net (code "93") (name "unconnected-(X9-VPP-Pad6)") (class "Default")
      (node (ref "X9") (pin "6") (pinfunction "VPP_6") (pintype "passive+no_connect"))
    )
  )
)
